# Power.net
KiCad netlist of a schematic drawn in Altium Designer
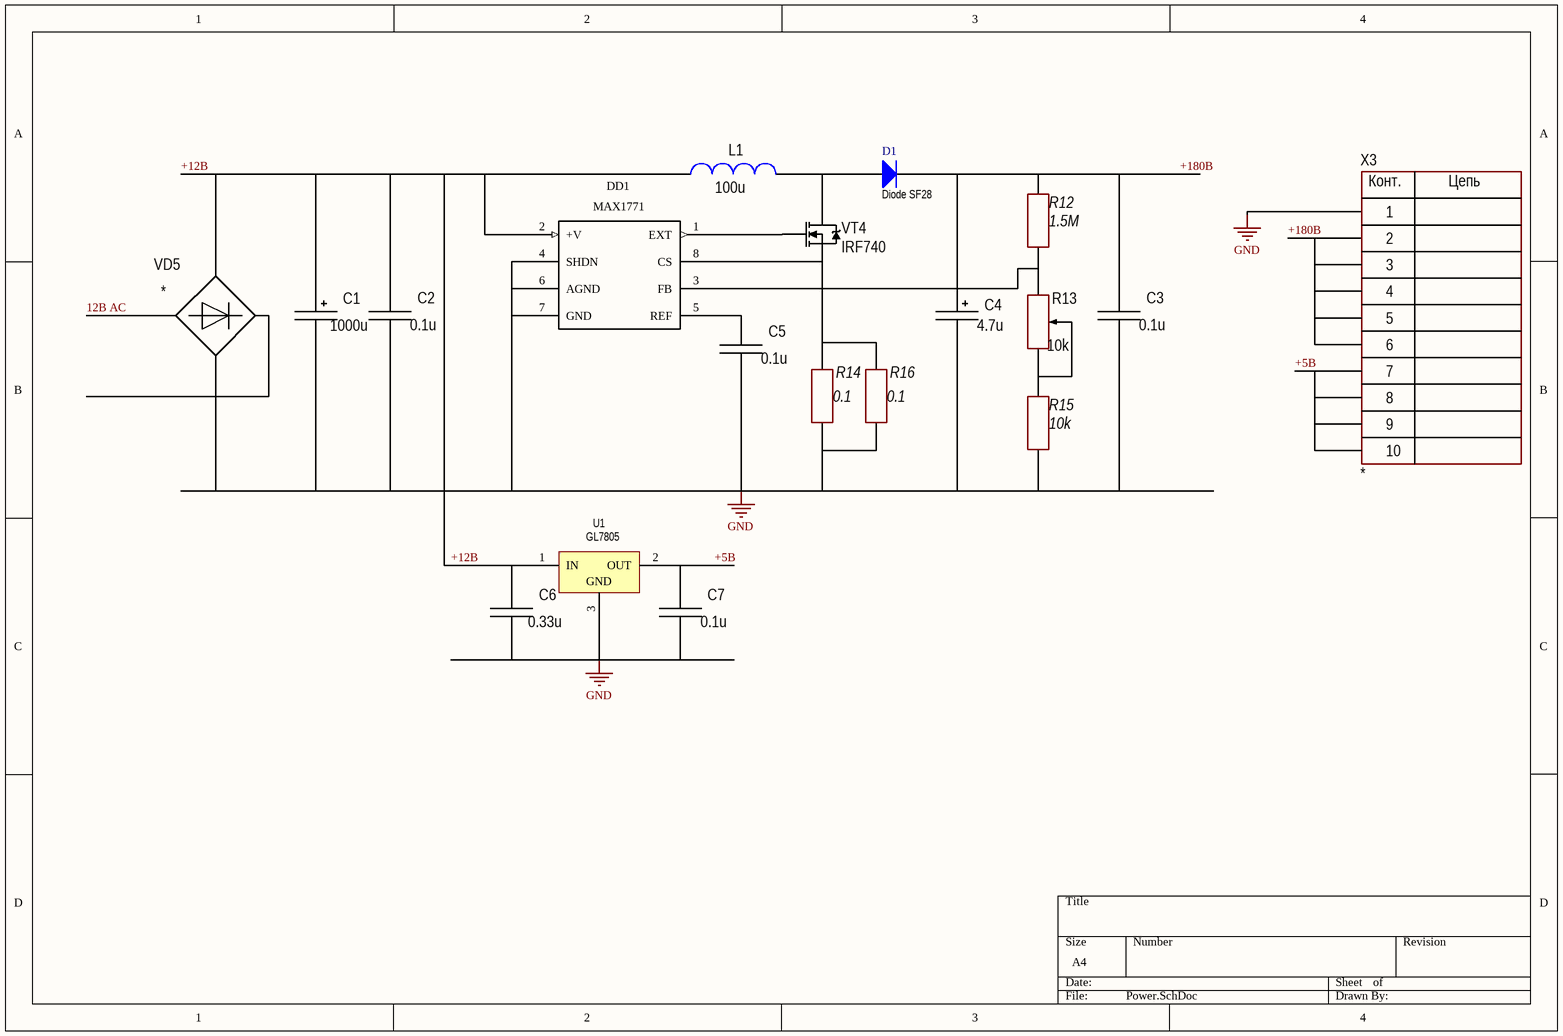
[diagram p0: Power.SchDoc]

(export (version "E")
  (design (tool "Eeschema 10.0.6"))
  (components
    (comp (ref "C1") (value "1000u") (footprint "D5C2H11") (libsource (lib "Discrete") (part "AlumCap")))
    (comp (ref "C2")
      (value "0.1u")
      (footprint "CAP: DEBB33D")
      (libsource (lib "Discrete") (part "Capacitor"))
    )
    (comp (ref "C3")
      (value "0.1u")
      (footprint "CAP: DEBB33D")
      (libsource (lib "Discrete") (part "Capacitor"))
    )
    (comp (ref "C4") (value "4.7u") (footprint "D8C3.5H12") (libsource (lib "Discrete") (part "AlumCap")))
    (comp (ref "C5")
      (value "0.1u")
      (footprint "CAP: DEBB33D")
      (libsource (lib "Discrete") (part "Capacitor"))
    )
    (comp (ref "C6")
      (value "0.33u")
      (footprint "CAP: DEBB33D")
      (libsource (lib "Discrete") (part "Capacitor"))
    )
    (comp (ref "C7")
      (value "0.1u")
      (footprint "CAP: DEBB33D")
      (libsource (lib "Discrete") (part "Capacitor"))
    )
    (comp (ref "D1")
      (value "Diode SF28")
      (footprint "DO-201AD")
      (description "3 Amp General Purpose Rectifier")
      (fields (field (name "PUBLISHER") "Altium Limited"))
      (libsource (lib "Miscellaneous Devices") (part "Diode 1N5402"))
    )
    (comp (ref "DD1")
      (value "MAX1771")
      (footprint "MAX1771_DIP8 - duplicate")
      (libsource (lib "MAX1771") (part "MAX1771"))
    )
    (comp (ref "L1") (value "100u") (footprint "IND: SRU1048") (libsource (lib "Discrete") (part "Inductor")))
    (comp (ref "R12")
      (value "1.5M")
      (footprint "MLT")
      (description "MLT")
      (libsource (lib "") (part "Resistor_1"))
    )
    (comp (ref "R13")
      (value "10k")
      (footprint "RES: 3296W")
      (libsource (lib "Discrete") (part "ADJ resistor"))
    )
    (comp (ref "R14")
      (value "0.1")
      (footprint "MLT")
      (description "MLT")
      (libsource (lib "Resistor_MLT") (part "Resistor"))
    )
    (comp (ref "R15")
      (value "10k")
      (footprint "MLT")
      (description "MLT")
      (libsource (lib "") (part "Resistor_1"))
    )
    (comp (ref "R16")
      (value "0.1")
      (footprint "MLT")
      (description "MLT")
      (libsource (lib "Resistor_MLT") (part "Resistor"))
    )
    (comp (ref "U1")
      (value "GL7805")
      (footprint "TO220VW")
      (description "2A Positive Voltage Regulator")
      (fields (field (name "PUBLISHER") "Altium Limited"))
      (libsource (lib "ST Power Mgt Voltage Regulator") (part "L78S05CV"))
    )
    (comp (ref "VD5")
      (value "*")
      (footprint "custom:DIOD: DF206S-G")
      (libsource (lib "Diods") (part "Bridge"))
    )
    (comp (ref "VT4")
      (value "IRF740")
      (footprint "TO220_123_H")
      (description "Mosfet")
      (libsource (lib "Transistor") (part "N-chanel"))
    )
    (comp (ref "X3")
      (value "*")
      (footprint "CON: S10B-PHD")
      (libsource (lib "Connectors") (part "10-Connector"))
    )
  )
  (nets
    (net (code "1") (name "/+5В") (class "Default")
      (node (ref "C7") (pin "1") (pinfunction "1_1") (pintype "power_in"))
      (node (ref "U1") (pin "2") (pinfunction "OUT_2") (pintype "power_in"))
      (node (ref "X3") (pin "10") (pinfunction "10_10") (pintype "power_in"))
      (node (ref "X3") (pin "7") (pinfunction "7_7") (pintype "power_in"))
      (node (ref "X3") (pin "8") (pinfunction "8_8") (pintype "power_in"))
      (node (ref "X3") (pin "9") (pinfunction "9_9") (pintype "power_in"))
    )
    (net (code "2") (name "/+12В") (class "Default")
      (node (ref "C1") (pin "1") (pinfunction "1_1") (pintype "power_in"))
      (node (ref "C2") (pin "1") (pinfunction "1_1") (pintype "power_in"))
      (node (ref "C6") (pin "1") (pinfunction "1_1") (pintype "power_in"))
      (node (ref "DD1") (pin "2") (pinfunction "+V_2") (pintype "input"))
      (node (ref "L1") (pin "2") (pinfunction "2_2") (pintype "passive"))
      (node (ref "U1") (pin "1") (pinfunction "IN_1") (pintype "power_in"))
      (node (ref "VD5") (pin "2") (pinfunction "2_2") (pintype "passive"))
    )
    (net (code "3") (name "/+180В") (class "Default")
      (node (ref "C3") (pin "1") (pinfunction "1_1") (pintype "power_in"))
      (node (ref "C4") (pin "1") (pinfunction "1_1") (pintype "power_in"))
      (node (ref "D1") (pin "2") (pinfunction "K_2") (pintype "passive"))
      (node (ref "R12") (pin "1") (pintype "passive"))
      (node (ref "X3") (pin "2") (pinfunction "2_2") (pintype "passive"))
      (node (ref "X3") (pin "3") (pinfunction "3_3") (pintype "power_in"))
      (node (ref "X3") (pin "4") (pinfunction "4_4") (pintype "power_in"))
      (node (ref "X3") (pin "5") (pinfunction "5_5") (pintype "power_in"))
      (node (ref "X3") (pin "6") (pinfunction "6_6") (pintype "power_in"))
    )
    (net (code "4") (name "/12В AC") (class "Default")
      (node (ref "VD5") (pin "1") (pinfunction "1_1") (pintype "passive"))
    )
    (net (code "5") (name "GND") (class "Default")
      (node (ref "C1") (pin "2") (pinfunction "2_2") (pintype "power_in"))
      (node (ref "C2") (pin "2") (pinfunction "2_2") (pintype "power_in"))
      (node (ref "C3") (pin "2") (pinfunction "2_2") (pintype "power_in"))
      (node (ref "C4") (pin "2") (pinfunction "2_2") (pintype "power_in"))
      (node (ref "C5") (pin "2") (pinfunction "2_2") (pintype "power_in"))
      (node (ref "C6") (pin "2") (pinfunction "2_2") (pintype "power_in"))
      (node (ref "C7") (pin "2") (pinfunction "2_2") (pintype "power_in"))
      (node (ref "DD1") (pin "4") (pinfunction "SHDN_4") (pintype "passive"))
      (node (ref "DD1") (pin "6") (pinfunction "AGND_6") (pintype "passive"))
      (node (ref "DD1") (pin "7") (pinfunction "GND_7") (pintype "passive"))
      (node (ref "R14") (pin "1") (pintype "passive"))
      (node (ref "R15") (pin "2") (pintype "passive"))
      (node (ref "R16") (pin "1") (pintype "passive"))
      (node (ref "U1") (pin "3") (pinfunction "GND_3") (pintype "power_in"))
      (node (ref "VD5") (pin "4") (pinfunction "4_4") (pintype "passive"))
      (node (ref "X3") (pin "1") (pinfunction "1_1") (pintype "passive"))
    )
    (net (code "6") (name "Net-(D1-A)") (class "Default")
      (node (ref "D1") (pin "1") (pinfunction "A_1") (pintype "passive"))
      (node (ref "L1") (pin "1") (pinfunction "1_1") (pintype "passive"))
      (node (ref "VT4") (pin "2") (pinfunction "D_2") (pintype "passive"))
    )
    (net (code "7") (name "Net-(DD1-CS)") (class "Default")
      (node (ref "DD1") (pin "8") (pinfunction "CS_8") (pintype "passive"))
      (node (ref "R14") (pin "2") (pintype "passive"))
      (node (ref "R16") (pin "2") (pintype "passive"))
      (node (ref "VT4") (pin "3") (pinfunction "S_3") (pintype "passive"))
    )
    (net (code "8") (name "Net-(DD1-EXT)") (class "Default")
      (node (ref "DD1") (pin "1") (pinfunction "EXT_1") (pintype "output"))
      (node (ref "VT4") (pin "1") (pinfunction "G_1") (pintype "passive"))
    )
    (net (code "9") (name "Net-(DD1-FB)") (class "Default")
      (node (ref "DD1") (pin "3") (pinfunction "FB_3") (pintype "passive"))
      (node (ref "R12") (pin "2") (pintype "passive"))
      (node (ref "R13") (pin "1") (pinfunction "1_1") (pintype "passive"))
    )
    (net (code "10") (name "Net-(DD1-REF)") (class "Default")
      (node (ref "C5") (pin "1") (pinfunction "1_1") (pintype "power_in"))
      (node (ref "DD1") (pin "5") (pinfunction "REF_5") (pintype "passive"))
    )
    (net (code "11") (name "Net-(R13-Pad2)") (class "Default")
      (node (ref "R13") (pin "2") (pinfunction "2_2") (pintype "passive"))
      (node (ref "R13") (pin "3") (pinfunction "3_3") (pintype "passive"))
      (node (ref "R15") (pin "1") (pintype "passive"))
    )
    (net (code "12") (name "unconnected-(VD5-Pad3)") (class "Default")
      (node (ref "VD5") (pin "3") (pinfunction "3_3") (pintype "passive"))
    )
  )
)
